# VisionInspect-S3_AltiumDesigner.net
KiCad netlist of a schematic drawn in Altium Designer
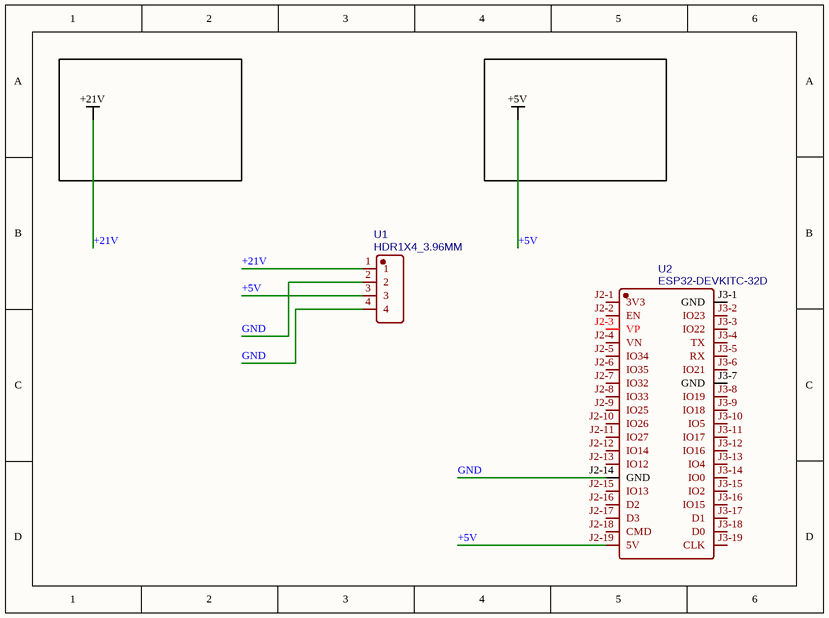
[diagram p0: VisionInspect-S3_AltiumDesigner.schdoc]

(export (version "E")
  (design (tool "Eeschema 10.0.6"))
  (components
    (comp (ref "U1")
      (value "HDR1X4_3.96MM")
      (fields (field (name "MANUFACTURER PART") "HDR1X4_3.96mm") (field (name "CONTRIBUTOR") "LCSC"))
      (libsource (lib "altium-import") (part "root_0_HDR1X4_3.96MM_"))
    )
    (comp (ref "U2")
      (value "ESP32-DEVKITC-32D")
      (fields
        (field (name "MANUFACTURER") "ESPRESSIF(乐鑫)")
        (field (name "MANUFACTURER PART") "ESP32-DevKitC-32D")
        (field (name "CONTRIBUTOR") "lcsc")
      )
      (libsource (lib "altium-import") (part "root_0_ESP32-DEVKITC-32D_"))
    )
  )
  (nets
    (net (code "1") (name "+5V") (class "Default")
      (node (ref "U1") (pin "3") (pinfunction "3_3") (pintype "passive"))
      (node (ref "U2") (pin "J2-19") (pinfunction "5V_J2-19") (pintype "passive"))
    )
    (net (code "2") (name "+21V") (class "Default")
      (node (ref "U1") (pin "1") (pinfunction "1_1") (pintype "passive"))
    )
    (net (code "3") (name "/GND") (class "Default")
      (node (ref "U1") (pin "2") (pinfunction "2_2") (pintype "passive"))
      (node (ref "U1") (pin "4") (pinfunction "4_4") (pintype "passive"))
      (node (ref "U2") (pin "J2-14") (pinfunction "GND_J2-14") (pintype "passive"))
    )
    (net (code "4") (name "unconnected-(U2-3V3-PadJ2-1)") (class "Default")
      (node (ref "U2") (pin "J2-1") (pinfunction "3V3_J2-1") (pintype "passive"))
    )
    (net (code "5") (name "unconnected-(U2-CLK-PadJ3-19)") (class "Default")
      (node (ref "U2") (pin "J3-19") (pinfunction "CLK_J3-19") (pintype "passive"))
    )
    (net (code "6") (name "unconnected-(U2-CMD-PadJ2-18)") (class "Default")
      (node (ref "U2") (pin "J2-18") (pinfunction "CMD_J2-18") (pintype "passive"))
    )
    (net (code "7") (name "unconnected-(U2-D0-PadJ3-18)") (class "Default")
      (node (ref "U2") (pin "J3-18") (pinfunction "D0_J3-18") (pintype "passive"))
    )
    (net (code "8") (name "unconnected-(U2-D1-PadJ3-17)") (class "Default")
      (node (ref "U2") (pin "J3-17") (pinfunction "D1_J3-17") (pintype "passive"))
    )
    (net (code "9") (name "unconnected-(U2-D2-PadJ2-16)") (class "Default")
      (node (ref "U2") (pin "J2-16") (pinfunction "D2_J2-16") (pintype "passive"))
    )
    (net (code "10") (name "unconnected-(U2-D3-PadJ2-17)") (class "Default")
      (node (ref "U2") (pin "J2-17") (pinfunction "D3_J2-17") (pintype "passive"))
    )
    (net (code "11") (name "unconnected-(U2-EN-PadJ2-2)") (class "Default")
      (node (ref "U2") (pin "J2-2") (pinfunction "EN_J2-2") (pintype "passive"))
    )
    (net (code "12") (name "unconnected-(U2-GND-PadJ3-1)") (class "Default")
      (node (ref "U2") (pin "J3-1") (pinfunction "GND_J3-1") (pintype "passive"))
    )
    (net (code "13") (name "unconnected-(U2-GND-PadJ3-7)") (class "Default")
      (node (ref "U2") (pin "J3-7") (pinfunction "GND_J3-7") (pintype "passive"))
    )
    (net (code "14") (name "unconnected-(U2-IO0-PadJ3-14)") (class "Default")
      (node (ref "U2") (pin "J3-14") (pinfunction "IO0_J3-14") (pintype "passive"))
    )
    (net (code "15") (name "unconnected-(U2-IO2-PadJ3-15)") (class "Default")
      (node (ref "U2") (pin "J3-15") (pinfunction "IO2_J3-15") (pintype "passive"))
    )
    (net (code "16") (name "unconnected-(U2-IO4-PadJ3-13)") (class "Default")
      (node (ref "U2") (pin "J3-13") (pinfunction "IO4_J3-13") (pintype "passive"))
    )
    (net (code "17") (name "unconnected-(U2-IO5-PadJ3-10)") (class "Default")
      (node (ref "U2") (pin "J3-10") (pinfunction "IO5_J3-10") (pintype "passive"))
    )
    (net (code "18") (name "unconnected-(U2-IO12-PadJ2-13)") (class "Default")
      (node (ref "U2") (pin "J2-13") (pinfunction "IO12_J2-13") (pintype "passive"))
    )
    (net (code "19") (name "unconnected-(U2-IO13-PadJ2-15)") (class "Default")
      (node (ref "U2") (pin "J2-15") (pinfunction "IO13_J2-15") (pintype "passive"))
    )
    (net (code "20") (name "unconnected-(U2-IO14-PadJ2-12)") (class "Default")
      (node (ref "U2") (pin "J2-12") (pinfunction "IO14_J2-12") (pintype "passive"))
    )
    (net (code "21") (name "unconnected-(U2-IO15-PadJ3-16)") (class "Default")
      (node (ref "U2") (pin "J3-16") (pinfunction "IO15_J3-16") (pintype "passive"))
    )
    (net (code "22") (name "unconnected-(U2-IO16-PadJ3-12)") (class "Default")
      (node (ref "U2") (pin "J3-12") (pinfunction "IO16_J3-12") (pintype "passive"))
    )
    (net (code "23") (name "unconnected-(U2-IO17-PadJ3-11)") (class "Default")
      (node (ref "U2") (pin "J3-11") (pinfunction "IO17_J3-11") (pintype "passive"))
    )
    (net (code "24") (name "unconnected-(U2-IO18-PadJ3-9)") (class "Default")
      (node (ref "U2") (pin "J3-9") (pinfunction "IO18_J3-9") (pintype "passive"))
    )
    (net (code "25") (name "unconnected-(U2-IO19-PadJ3-8)") (class "Default")
      (node (ref "U2") (pin "J3-8") (pinfunction "IO19_J3-8") (pintype "passive"))
    )
    (net (code "26") (name "unconnected-(U2-IO21-PadJ3-6)") (class "Default")
      (node (ref "U2") (pin "J3-6") (pinfunction "IO21_J3-6") (pintype "passive"))
    )
    (net (code "27") (name "unconnected-(U2-IO22-PadJ3-3)") (class "Default")
      (node (ref "U2") (pin "J3-3") (pinfunction "IO22_J3-3") (pintype "passive"))
    )
    (net (code "28") (name "unconnected-(U2-IO23-PadJ3-2)") (class "Default")
      (node (ref "U2") (pin "J3-2") (pinfunction "IO23_J3-2") (pintype "passive"))
    )
    (net (code "29") (name "unconnected-(U2-IO25-PadJ2-9)") (class "Default")
      (node (ref "U2") (pin "J2-9") (pinfunction "IO25_J2-9") (pintype "passive"))
    )
    (net (code "30") (name "unconnected-(U2-IO26-PadJ2-10)") (class "Default")
      (node (ref "U2") (pin "J2-10") (pinfunction "IO26_J2-10") (pintype "passive"))
    )
    (net (code "31") (name "unconnected-(U2-IO27-PadJ2-11)") (class "Default")
      (node (ref "U2") (pin "J2-11") (pinfunction "IO27_J2-11") (pintype "passive"))
    )
    (net (code "32") (name "unconnected-(U2-IO32-PadJ2-7)") (class "Default")
      (node (ref "U2") (pin "J2-7") (pinfunction "IO32_J2-7") (pintype "passive"))
    )
    (net (code "33") (name "unconnected-(U2-IO33-PadJ2-8)") (class "Default")
      (node (ref "U2") (pin "J2-8") (pinfunction "IO33_J2-8") (pintype "passive"))
    )
    (net (code "34") (name "unconnected-(U2-IO34-PadJ2-5)") (class "Default")
      (node (ref "U2") (pin "J2-5") (pinfunction "IO34_J2-5") (pintype "passive"))
    )
    (net (code "35") (name "unconnected-(U2-IO35-PadJ2-6)") (class "Default")
      (node (ref "U2") (pin "J2-6") (pinfunction "IO35_J2-6") (pintype "passive"))
    )
    (net (code "36") (name "unconnected-(U2-RX-PadJ3-5)") (class "Default")
      (node (ref "U2") (pin "J3-5") (pinfunction "RX_J3-5") (pintype "passive"))
    )
    (net (code "37") (name "unconnected-(U2-TX-PadJ3-4)") (class "Default")
      (node (ref "U2") (pin "J3-4") (pinfunction "TX_J3-4") (pintype "passive"))
    )
    (net (code "38") (name "unconnected-(U2-VN-PadJ2-4)") (class "Default")
      (node (ref "U2") (pin "J2-4") (pinfunction "VN_J2-4") (pintype "passive"))
    )
    (net (code "39") (name "unconnected-(U2-VP-PadJ2-3)") (class "Default")
      (node (ref "U2") (pin "J2-3") (pinfunction "VP_J2-3") (pintype "passive"))
    )
  )
)
